# furby_shield_v1.net
KiCad netlist of a schematic drawn in EAGLE
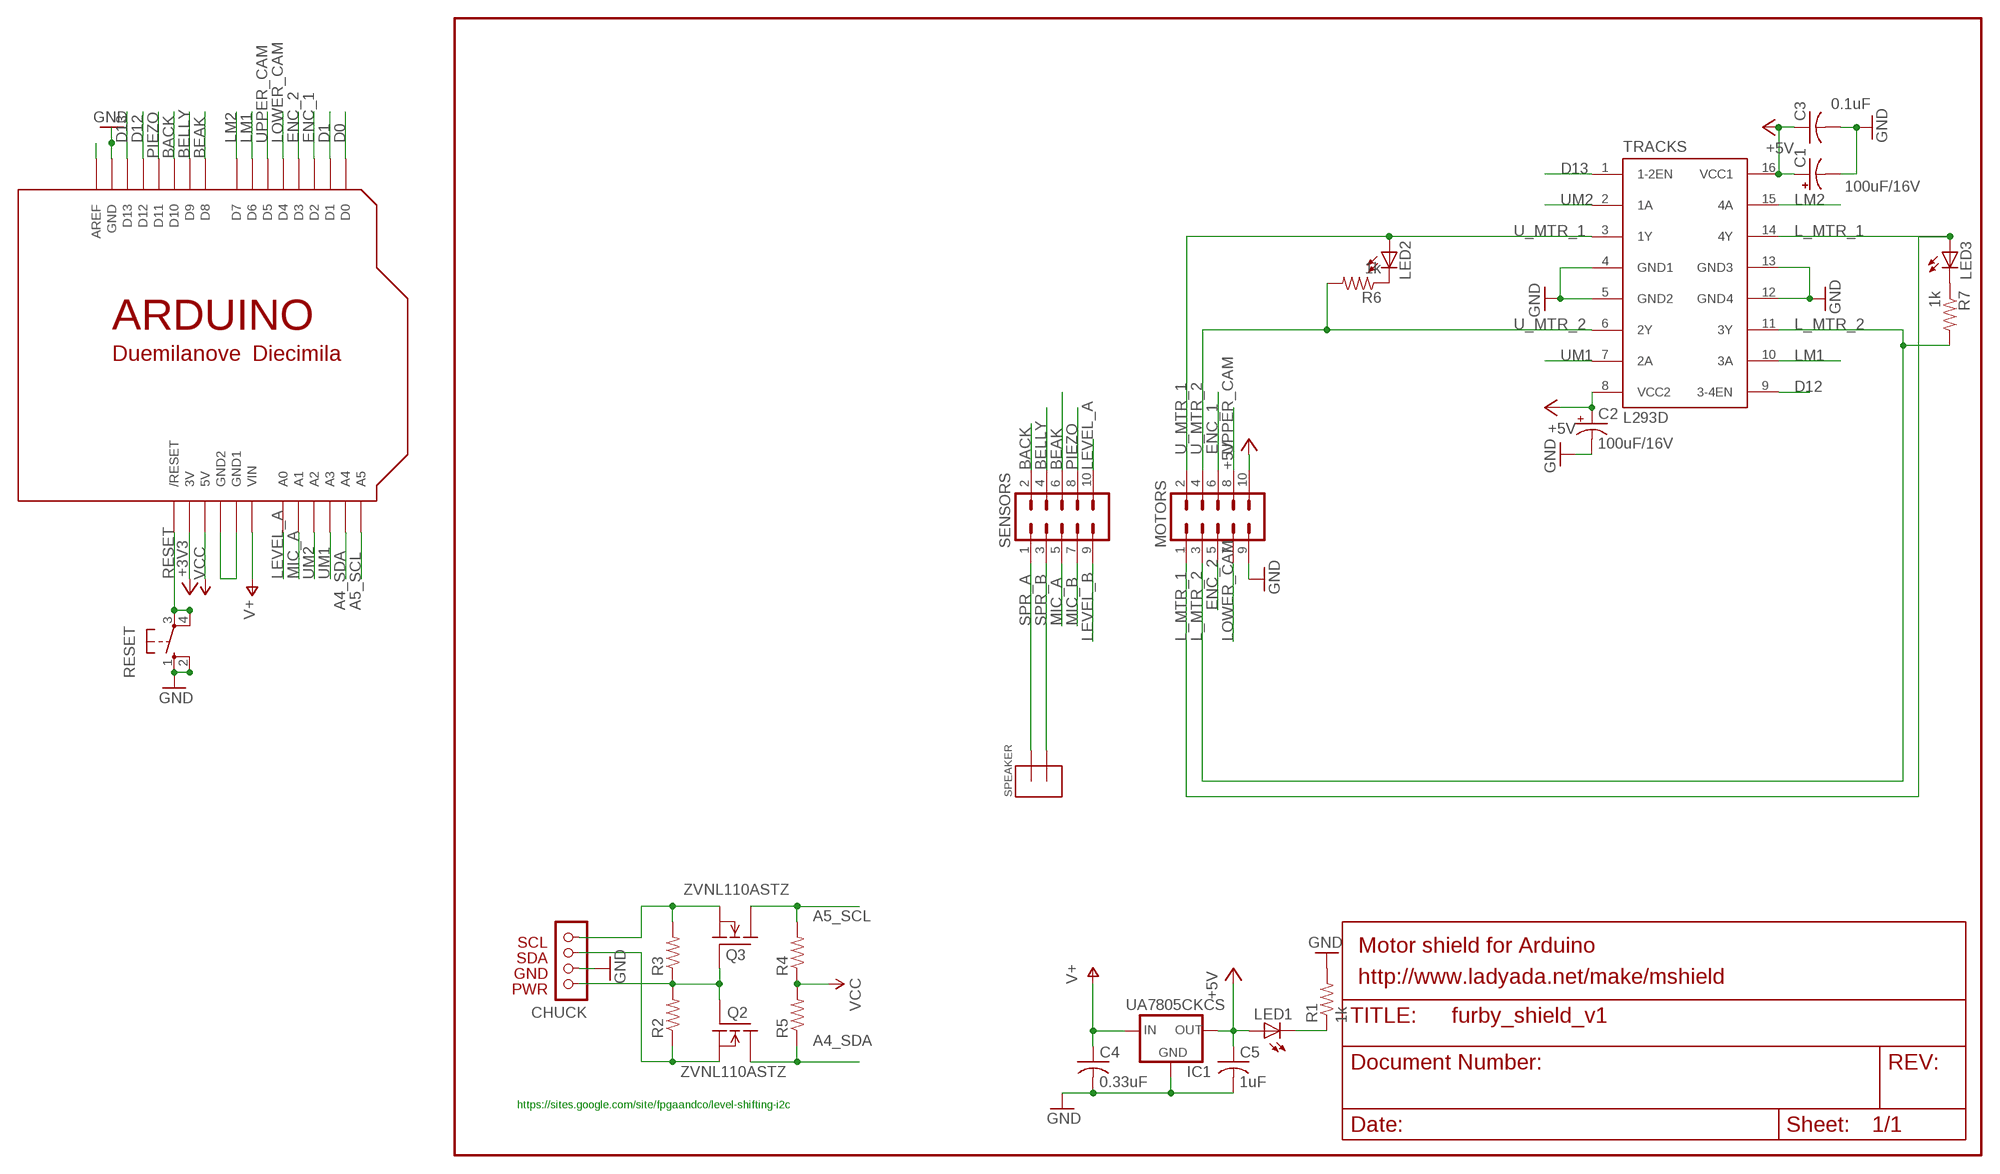
[diagram p0: schematic, sheet 1]

(export (version "E")
  (design (tool "Eeschema 10.0.6"))
  (components
    (comp (ref "C1")
      (value "100uF/16V")
      (footprint "eagle-import:E2,5-6")
      (libsource (lib "eagle-import") (part "CPOL-USE2.5-6"))
    )
    (comp (ref "C2")
      (value "100uF/16V")
      (footprint "eagle-import:E2,5-6")
      (libsource (lib "eagle-import") (part "CPOL-USE2.5-6"))
    )
    (comp (ref "C3")
      (value "0.1uF")
      (footprint "eagle-import:C025-025X050")
      (libsource (lib "eagle-import") (part "rcl-ez_C-US025-025X050"))
    )
    (comp (ref "C4")
      (value "0.33uF")
      (footprint "eagle-import:C025-024X044")
      (libsource (lib "eagle-import") (part "C-US025-024X044"))
    )
    (comp (ref "C5")
      (value "1uF")
      (footprint "eagle-import:C025-024X044")
      (libsource (lib "eagle-import") (part "C-US025-024X044"))
    )
    (comp (ref "CHUCK")
      (value "NUNCHUCK")
      (footprint "eagle-import:CONN")
      (libsource (lib "eagle-import") (part "NUNCHUCK"))
    )
    (comp (ref "IC1")
      (value "UA7805CKCS")
      (footprint "eagle-import:TO-220-ALT")
      (libsource (lib "eagle-import") (part "V_REG_78XX-TO-220"))
    )
    (comp (ref "LED1")
      (value "LED3MM")
      (footprint "eagle-import:LED3MM")
      (libsource (lib "eagle-import") (part "LED3MM"))
    )
    (comp (ref "LED2")
      (value "LED3MM")
      (footprint "eagle-import:LED3MM")
      (libsource (lib "eagle-import") (part "LED3MM"))
    )
    (comp (ref "LED3")
      (value "LED3MM")
      (footprint "eagle-import:LED3MM")
      (libsource (lib "eagle-import") (part "LED3MM"))
    )
    (comp (ref "MOTORS")
      (value "M05X2SHD")
      (footprint "eagle-import:2X5-SHROUDED")
      (libsource (lib "eagle-import") (part "M05X2SHD"))
    )
    (comp (ref "Q2")
      (value "ZVNL110ASTZ")
      (footprint "eagle-import:TO92-INLINE")
      (libsource (lib "eagle-import") (part "FQN1N50CI"))
    )
    (comp (ref "Q3")
      (value "ZVNL110ASTZ")
      (footprint "eagle-import:TO92-INLINE")
      (libsource (lib "eagle-import") (part "FQN1N50CI"))
    )
    (comp (ref "R1")
      (value "1k")
      (footprint "eagle-import:0204_5")
      (libsource (lib "eagle-import") (part "R-US_0204/5"))
    )
    (comp (ref "R2")
      (value "R-US_0204/7")
      (footprint "eagle-import:0204_7")
      (libsource (lib "eagle-import") (part "R-US_0204/7"))
    )
    (comp (ref "R3")
      (value "R-US_0204/7")
      (footprint "eagle-import:0204_7")
      (libsource (lib "eagle-import") (part "R-US_0204/7"))
    )
    (comp (ref "R4")
      (value "R-US_0204/7")
      (footprint "eagle-import:0204_7")
      (libsource (lib "eagle-import") (part "R-US_0204/7"))
    )
    (comp (ref "R5")
      (value "R-US_0204/7")
      (footprint "eagle-import:0204_7")
      (libsource (lib "eagle-import") (part "R-US_0204/7"))
    )
    (comp (ref "R6")
      (value "1k")
      (footprint "eagle-import:0204_5")
      (libsource (lib "eagle-import") (part "R-US_0204/5"))
    )
    (comp (ref "R7")
      (value "1k")
      (footprint "eagle-import:0204_5")
      (libsource (lib "eagle-import") (part "R-US_0204/5"))
    )
    (comp (ref "RESET")
      (value "10-XX")
      (footprint "eagle-import:B3F-10XX")
      (libsource (lib "eagle-import") (part "10-XX"))
    )
    (comp (ref "SENSORS")
      (value "M05X2SHD")
      (footprint "eagle-import:2X5-SHROUDED")
      (libsource (lib "eagle-import") (part "M05X2SHD"))
    )
    (comp (ref "SPEAKER")
      (value "TERMINAL2")
      (footprint "eagle-import:TERMINAL_2")
      (libsource (lib "eagle-import") (part "TERMINAL2"))
    )
    (comp (ref "TRACKS")
      (value "L293D")
      (footprint "eagle-import:DIL16")
      (libsource (lib "eagle-import") (part "L293E"))
    )
    (comp (ref "U$1")
      (value "ARDUINO-NOHOLE")
      (footprint "eagle-import:ARDUINO-NOHOLE")
      (libsource (lib "eagle-import") (part "ARDUINO-NOHOLE"))
    )
  )
  (nets
    (net (code "1") (name "+3V3") (class "Default")
      (node (ref "CHUCK") (pin "PWR") (pinfunction "PWR_PWR") (pintype "power_in"))
      (node (ref "Q2") (pin "2") (pinfunction "G_2") (pintype "passive"))
      (node (ref "Q3") (pin "2") (pinfunction "G_2") (pintype "passive"))
      (node (ref "R2") (pin "2") (pinfunction "2_2") (pintype "passive"))
      (node (ref "R3") (pin "1") (pinfunction "1_1") (pintype "passive"))
      (node (ref "U$1") (pin "3V") (pinfunction "3V_3V") (pintype "power_in"))
    )
    (net (code "2") (name "+5V") (class "Default")
      (node (ref "C1") (pin "+") (pinfunction "+_+") (pintype "passive"))
      (node (ref "C2") (pin "+") (pinfunction "+_+") (pintype "passive"))
      (node (ref "C3") (pin "1") (pinfunction "1_1") (pintype "passive"))
      (node (ref "C5") (pin "1") (pinfunction "1_1") (pintype "passive"))
      (node (ref "IC1") (pin "OUT") (pinfunction "OUT_OUT") (pintype "output"))
      (node (ref "LED1") (pin "A") (pinfunction "A_A") (pintype "passive"))
      (node (ref "MOTORS") (pin "10") (pinfunction "10_10") (pintype "passive"))
      (node (ref "TRACKS") (pin "16") (pinfunction "VCC1_16") (pintype "power_in"))
      (node (ref "TRACKS") (pin "8") (pinfunction "VCC2_8") (pintype "power_in"))
    )
    (net (code "3") (name "/A4_SDA") (class "Default")
      (node (ref "Q2") (pin "1") (pinfunction "D_1") (pintype "passive"))
      (node (ref "R5") (pin "1") (pinfunction "1_1") (pintype "passive"))
      (node (ref "U$1") (pin "A4") (pinfunction "A4_A4") (pintype "bidirectional"))
    )
    (net (code "4") (name "/A5_SCL") (class "Default")
      (node (ref "Q3") (pin "1") (pinfunction "D_1") (pintype "passive"))
      (node (ref "R4") (pin "2") (pinfunction "2_2") (pintype "passive"))
      (node (ref "U$1") (pin "A5") (pinfunction "A5_A5") (pintype "bidirectional"))
    )
    (net (code "5") (name "/BACK") (class "Default")
      (node (ref "SENSORS") (pin "2") (pinfunction "2_2") (pintype "passive"))
      (node (ref "U$1") (pin "D10") (pinfunction "D10_D10") (pintype "bidirectional"))
    )
    (net (code "6") (name "/BEAK") (class "Default")
      (node (ref "SENSORS") (pin "6") (pinfunction "6_6") (pintype "passive"))
      (node (ref "U$1") (pin "D8") (pinfunction "D8_D8") (pintype "bidirectional"))
    )
    (net (code "7") (name "/BELLY") (class "Default")
      (node (ref "SENSORS") (pin "4") (pinfunction "4_4") (pintype "passive"))
      (node (ref "U$1") (pin "D9") (pinfunction "D9_D9") (pintype "bidirectional"))
    )
    (net (code "8") (name "/D0") (class "Default")
      (node (ref "U$1") (pin "D0") (pinfunction "D0_D0") (pintype "bidirectional"))
    )
    (net (code "9") (name "/D1") (class "Default")
      (node (ref "U$1") (pin "D1") (pinfunction "D1_D1") (pintype "bidirectional"))
    )
    (net (code "10") (name "/D12") (class "Default")
      (node (ref "TRACKS") (pin "9") (pinfunction "3-4EN_9") (pintype "input"))
      (node (ref "U$1") (pin "D12") (pinfunction "D12_D12") (pintype "bidirectional"))
    )
    (net (code "11") (name "/D13") (class "Default")
      (node (ref "TRACKS") (pin "1") (pinfunction "1-2EN_1") (pintype "input"))
      (node (ref "U$1") (pin "D13") (pinfunction "D13_D13") (pintype "bidirectional"))
    )
    (net (code "12") (name "/ENC_1") (class "Default")
      (node (ref "MOTORS") (pin "6") (pinfunction "6_6") (pintype "passive"))
      (node (ref "U$1") (pin "D2") (pinfunction "D2_D2") (pintype "bidirectional"))
    )
    (net (code "13") (name "/ENC_2") (class "Default")
      (node (ref "MOTORS") (pin "5") (pinfunction "5_5") (pintype "passive"))
      (node (ref "U$1") (pin "D3") (pinfunction "D3_D3") (pintype "bidirectional"))
    )
    (net (code "14") (name "/LEVEL_A") (class "Default")
      (node (ref "SENSORS") (pin "10") (pinfunction "10_10") (pintype "passive"))
      (node (ref "U$1") (pin "A0") (pinfunction "A0_A0") (pintype "bidirectional"))
    )
    (net (code "15") (name "/LEVEL_B") (class "Default")
      (node (ref "SENSORS") (pin "9") (pinfunction "9_9") (pintype "passive"))
    )
    (net (code "16") (name "/LM1") (class "Default")
      (node (ref "TRACKS") (pin "10") (pinfunction "3A_10") (pintype "input"))
      (node (ref "U$1") (pin "D6") (pinfunction "D6_D6") (pintype "bidirectional"))
    )
    (net (code "17") (name "/LM2") (class "Default")
      (node (ref "TRACKS") (pin "15") (pinfunction "4A_15") (pintype "input"))
      (node (ref "U$1") (pin "D7") (pinfunction "D7_D7") (pintype "bidirectional"))
    )
    (net (code "18") (name "/LOWER_CAM") (class "Default")
      (node (ref "MOTORS") (pin "7") (pinfunction "7_7") (pintype "passive"))
      (node (ref "U$1") (pin "D4") (pinfunction "D4_D4") (pintype "bidirectional"))
    )
    (net (code "19") (name "/L_MTR_1") (class "Default")
      (node (ref "LED3") (pin "A") (pinfunction "A_A") (pintype "passive"))
      (node (ref "MOTORS") (pin "1") (pinfunction "1_1") (pintype "passive"))
      (node (ref "TRACKS") (pin "14") (pinfunction "4Y_14") (pintype "output"))
    )
    (net (code "20") (name "/L_MTR_2") (class "Default")
      (node (ref "MOTORS") (pin "3") (pinfunction "3_3") (pintype "passive"))
      (node (ref "R7") (pin "2") (pinfunction "2_2") (pintype "passive"))
      (node (ref "TRACKS") (pin "11") (pinfunction "3Y_11") (pintype "output"))
    )
    (net (code "21") (name "/MIC_A") (class "Default")
      (node (ref "SENSORS") (pin "5") (pinfunction "5_5") (pintype "passive"))
      (node (ref "U$1") (pin "A1") (pinfunction "A1_A1") (pintype "bidirectional"))
    )
    (net (code "22") (name "/MIC_B") (class "Default")
      (node (ref "SENSORS") (pin "7") (pinfunction "7_7") (pintype "passive"))
    )
    (net (code "23") (name "/PIEZO") (class "Default")
      (node (ref "SENSORS") (pin "8") (pinfunction "8_8") (pintype "passive"))
      (node (ref "U$1") (pin "D11") (pinfunction "D11_D11") (pintype "bidirectional"))
    )
    (net (code "24") (name "/RESET") (class "Default")
      (node (ref "RESET") (pin "3") (pinfunction "P_3") (pintype "passive"))
      (node (ref "RESET") (pin "4") (pinfunction "P1_4") (pintype "passive"))
      (node (ref "U$1") (pin "RESET") (pinfunction "/RESET_RESET") (pintype "bidirectional"))
    )
    (net (code "25") (name "/SPR_A") (class "Default")
      (node (ref "SENSORS") (pin "1") (pinfunction "1_1") (pintype "passive"))
      (node (ref "SPEAKER") (pin "P$1") (pinfunction "P$1_P$1") (pintype "bidirectional"))
    )
    (net (code "26") (name "/SPR_B") (class "Default")
      (node (ref "SENSORS") (pin "3") (pinfunction "3_3") (pintype "passive"))
      (node (ref "SPEAKER") (pin "P$2") (pinfunction "P$2_P$2") (pintype "bidirectional"))
    )
    (net (code "27") (name "/UM1") (class "Default")
      (node (ref "TRACKS") (pin "7") (pinfunction "2A_7") (pintype "input"))
      (node (ref "U$1") (pin "A3") (pinfunction "A3_A3") (pintype "bidirectional"))
    )
    (net (code "28") (name "/UM2") (class "Default")
      (node (ref "TRACKS") (pin "2") (pinfunction "1A_2") (pintype "input"))
      (node (ref "U$1") (pin "A2") (pinfunction "A2_A2") (pintype "bidirectional"))
    )
    (net (code "29") (name "/UPPER_CAM") (class "Default")
      (node (ref "MOTORS") (pin "8") (pinfunction "8_8") (pintype "passive"))
      (node (ref "U$1") (pin "D5") (pinfunction "D5_D5") (pintype "bidirectional"))
    )
    (net (code "30") (name "/U_MTR_1") (class "Default")
      (node (ref "LED2") (pin "A") (pinfunction "A_A") (pintype "passive"))
      (node (ref "MOTORS") (pin "2") (pinfunction "2_2") (pintype "passive"))
      (node (ref "TRACKS") (pin "3") (pinfunction "1Y_3") (pintype "output"))
    )
    (net (code "31") (name "/U_MTR_2") (class "Default")
      (node (ref "MOTORS") (pin "4") (pinfunction "4_4") (pintype "passive"))
      (node (ref "R6") (pin "2") (pinfunction "2_2") (pintype "passive"))
      (node (ref "TRACKS") (pin "6") (pinfunction "2Y_6") (pintype "output"))
    )
    (net (code "32") (name "GND") (class "Default")
      (node (ref "C1") (pin "-") (pinfunction "-_-") (pintype "passive"))
      (node (ref "C2") (pin "-") (pinfunction "-_-") (pintype "passive"))
      (node (ref "C3") (pin "2") (pinfunction "2_2") (pintype "passive"))
      (node (ref "C4") (pin "2") (pinfunction "2_2") (pintype "passive"))
      (node (ref "C5") (pin "2") (pinfunction "2_2") (pintype "passive"))
      (node (ref "CHUCK") (pin "GND") (pinfunction "GND_GND") (pintype "passive"))
      (node (ref "IC1") (pin "GND") (pinfunction "GND_GND") (pintype "input"))
      (node (ref "MOTORS") (pin "9") (pinfunction "9_9") (pintype "passive"))
      (node (ref "R1") (pin "2") (pinfunction "2_2") (pintype "passive"))
      (node (ref "RESET") (pin "1") (pinfunction "S_1") (pintype "passive"))
      (node (ref "RESET") (pin "2") (pinfunction "S1_2") (pintype "passive"))
      (node (ref "TRACKS") (pin "12") (pinfunction "GND4_12") (pintype "power_in"))
      (node (ref "TRACKS") (pin "13") (pinfunction "GND3_13") (pintype "power_in"))
      (node (ref "TRACKS") (pin "4") (pinfunction "GND1_4") (pintype "power_in"))
      (node (ref "TRACKS") (pin "5") (pinfunction "GND2_5") (pintype "power_in"))
      (node (ref "U$1") (pin "GND") (pinfunction "GND_GND") (pintype "power_in"))
      (node (ref "U$1") (pin "GND1") (pinfunction "GND1_GND1") (pintype "power_in"))
      (node (ref "U$1") (pin "GND2") (pinfunction "GND2_GND2") (pintype "power_in"))
    )
    (net (code "33") (name "Net-(LED1-C)") (class "Default")
      (node (ref "LED1") (pin "K") (pinfunction "C_K") (pintype "passive"))
      (node (ref "R1") (pin "1") (pinfunction "1_1") (pintype "passive"))
    )
    (net (code "34") (name "Net-(LED2-C)") (class "Default")
      (node (ref "LED2") (pin "K") (pinfunction "C_K") (pintype "passive"))
      (node (ref "R6") (pin "1") (pinfunction "1_1") (pintype "passive"))
    )
    (net (code "35") (name "Net-(LED3-C)") (class "Default")
      (node (ref "LED3") (pin "K") (pinfunction "C_K") (pintype "passive"))
      (node (ref "R7") (pin "1") (pinfunction "1_1") (pintype "passive"))
    )
    (net (code "36") (name "Net-(Q2-S)") (class "Default")
      (node (ref "CHUCK") (pin "SDA") (pinfunction "SDA_SDA") (pintype "bidirectional"))
      (node (ref "Q2") (pin "3") (pinfunction "S_3") (pintype "passive"))
      (node (ref "R2") (pin "1") (pinfunction "1_1") (pintype "passive"))
    )
    (net (code "37") (name "Net-(Q3-S)") (class "Default")
      (node (ref "CHUCK") (pin "SCL") (pinfunction "SCL_SCL") (pintype "bidirectional"))
      (node (ref "Q3") (pin "3") (pinfunction "S_3") (pintype "passive"))
      (node (ref "R3") (pin "2") (pinfunction "2_2") (pintype "passive"))
    )
    (net (code "38") (name "V+") (class "Default")
      (node (ref "C4") (pin "1") (pinfunction "1_1") (pintype "passive"))
      (node (ref "IC1") (pin "IN") (pinfunction "IN_IN") (pintype "input"))
      (node (ref "U$1") (pin "VIN") (pinfunction "VIN_VIN") (pintype "power_in"))
    )
    (net (code "39") (name "VCC") (class "Default")
      (node (ref "R4") (pin "1") (pinfunction "1_1") (pintype "passive"))
      (node (ref "R5") (pin "2") (pinfunction "2_2") (pintype "passive"))
      (node (ref "U$1") (pin "5V") (pinfunction "5V_5V") (pintype "power_in"))
      (node (ref "U$1") (pin "AREF") (pinfunction "AREF_AREF") (pintype "bidirectional"))
    )
  )
)
